# REG113-33_sch.net
KiCad netlist of a schematic drawn in Altium Designer
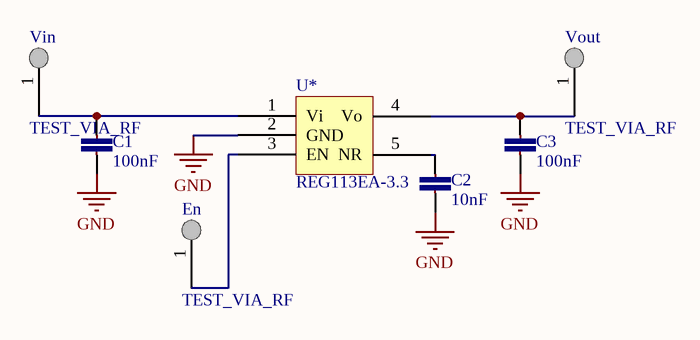
[diagram p0: REG113-33_sch.SchDoc]

(export (version "E")
  (design (tool "Eeschema 10.0.6"))
  (components
    (comp (ref "C1")
      (value "100nF")
      (footprint "0402-CAP")
      (description "CAP CER 0.1UF 50V 10% X7R 0402")
      (fields (field (name "PART NO") "C1005X7R1H104K050BB"))
      (libsource (lib "IMBEL") (part "CAPACITOR"))
    )
    (comp (ref "C2")
      (value "10nF")
      (footprint "0402-CAP")
      (description "CAP CER 10000PF 25V 5% X7R 0402")
      (fields (field (name "PART NO") "GRM155R71E103JA01J"))
      (libsource (lib "IMBEL") (part "CAPACITOR"))
    )
    (comp (ref "C3")
      (value "100nF")
      (footprint "0402-CAP")
      (description "CAP CER 0.1UF 50V 10% X7R 0402")
      (fields (field (name "PART NO") "C1005X7R1H104K050BB"))
      (libsource (lib "IMBEL") (part "CAPACITOR"))
    )
    (comp (ref "En")
      (value "TEST_VIA_RF")
      (footprint "New footprint 1")
      (description "Test VIA for RF circuits")
      (libsource (lib "IMBEL") (part "TEST_VIA"))
    )
    (comp (ref "U*")
      (value "REG113EA-3.3")
      (footprint "SOT95P280X145-5N")
      (description "IC REG LINEAR 3.3V 400MA 8VSSOP")
      (libsource (lib "IMBEL") (part "REG113"))
    )
    (comp (ref "Vin")
      (value "TEST_VIA_RF")
      (footprint "New footprint 1")
      (description "Test VIA for RF circuits")
      (libsource (lib "IMBEL") (part "TEST_VIA"))
    )
    (comp (ref "Vout")
      (value "TEST_VIA_RF")
      (footprint "New footprint 1")
      (description "Test VIA for RF circuits")
      (libsource (lib "IMBEL") (part "TEST_VIA"))
    )
  )
  (nets
    (net (code "1") (name "GND") (class "Default")
      (node (ref "C1") (pin "2") (pinfunction "2_2") (pintype "passive"))
      (node (ref "C2") (pin "2") (pinfunction "2_2") (pintype "passive"))
      (node (ref "C3") (pin "2") (pinfunction "2_2") (pintype "passive"))
      (node (ref "U*") (pin "2") (pinfunction "GND_2") (pintype "passive"))
    )
    (net (code "2") (name "Net-(U*-EN)") (class "Default")
      (node (ref "En") (pin "1") (pinfunction "1_1") (pintype "passive"))
      (node (ref "U*") (pin "3") (pinfunction "EN_3") (pintype "passive"))
    )
    (net (code "3") (name "Net-(U*-NR)") (class "Default")
      (node (ref "C2") (pin "1") (pinfunction "1_1") (pintype "passive"))
      (node (ref "U*") (pin "5") (pinfunction "NR_5") (pintype "passive"))
    )
    (net (code "4") (name "Net-(U*-Vi)") (class "Default")
      (node (ref "C1") (pin "1") (pinfunction "1_1") (pintype "passive"))
      (node (ref "U*") (pin "1") (pinfunction "Vi_1") (pintype "passive"))
      (node (ref "Vin") (pin "1") (pinfunction "1_1") (pintype "passive"))
    )
    (net (code "5") (name "Net-(U*-Vo)") (class "Default")
      (node (ref "C3") (pin "1") (pinfunction "1_1") (pintype "passive"))
      (node (ref "U*") (pin "4") (pinfunction "Vo_4") (pintype "passive"))
      (node (ref "Vout") (pin "1") (pinfunction "1_1") (pintype "passive"))
    )
  )
)
